# M720db.net
KiCad netlist of a schematic drawn in EAGLE
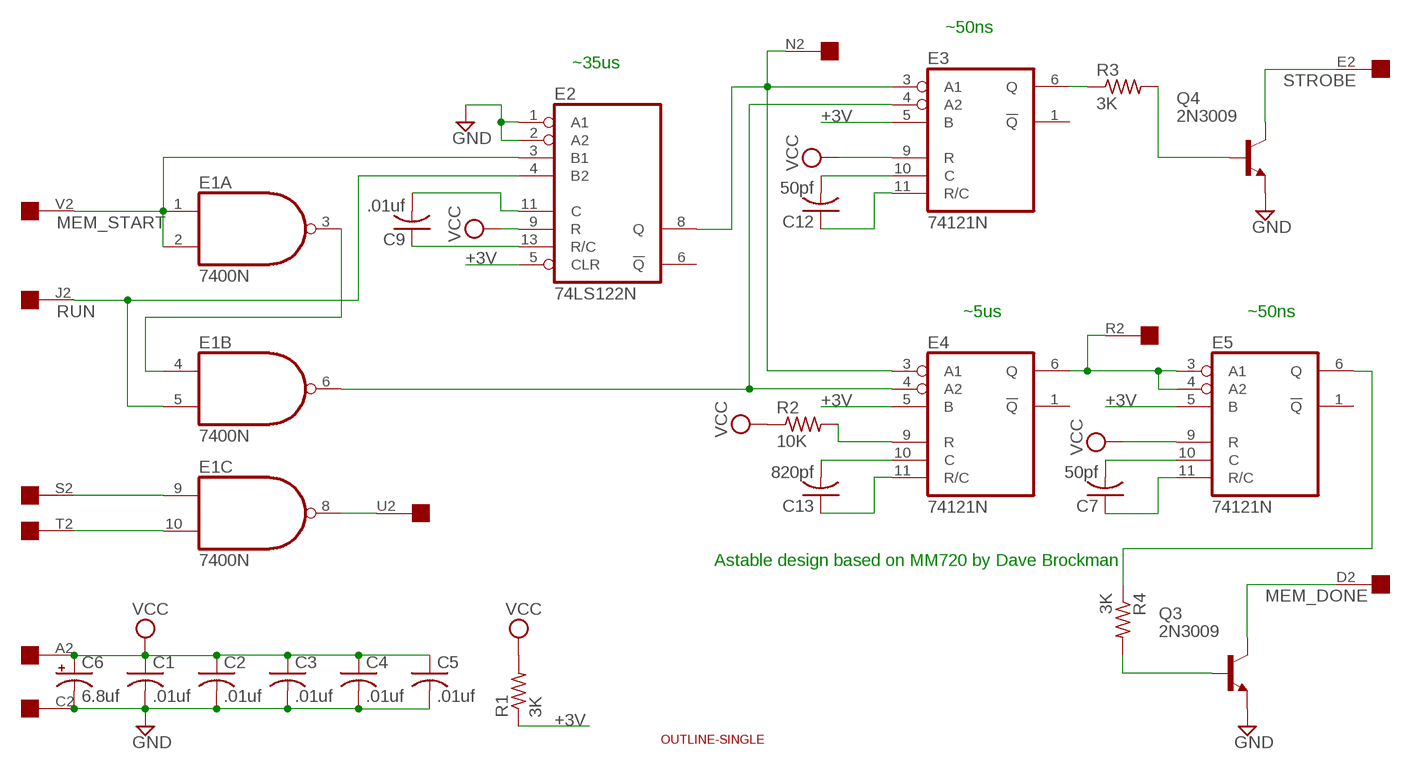
[diagram p0: schematic, sheet 1]

(export (version "E")
  (design (tool "Eeschema 10.0.6"))
  (components
    (comp (ref "C1")
      (value ".01uf")
      (footprint "eagle-import:C050-025X075")
      (libsource (lib "eagle-import") (part "C-US050-025X075"))
    )
    (comp (ref "C2")
      (value ".01uf")
      (footprint "eagle-import:C050-025X075")
      (libsource (lib "eagle-import") (part "C-US050-025X075"))
    )
    (comp (ref "C3")
      (value ".01uf")
      (footprint "eagle-import:C050-025X075")
      (libsource (lib "eagle-import") (part "C-US050-025X075"))
    )
    (comp (ref "C4")
      (value ".01uf")
      (footprint "eagle-import:C050-025X075")
      (libsource (lib "eagle-import") (part "C-US050-025X075"))
    )
    (comp (ref "C5")
      (value ".01uf")
      (footprint "eagle-import:C050-025X075")
      (libsource (lib "eagle-import") (part "C-US050-025X075"))
    )
    (comp (ref "C6")
      (value "6.8uf")
      (footprint "eagle-import:E15-5")
      (libsource (lib "eagle-import") (part "CPOL-USE15-5AXIAL"))
    )
    (comp (ref "C7")
      (value "50pf")
      (footprint "eagle-import:C050-025X075")
      (libsource (lib "eagle-import") (part "C-US050-025X075"))
    )
    (comp (ref "C9")
      (value ".01uf")
      (footprint "eagle-import:C050-025X075")
      (libsource (lib "eagle-import") (part "C-US050-025X075"))
    )
    (comp (ref "C12")
      (value "50pf")
      (footprint "eagle-import:C050-025X075")
      (libsource (lib "eagle-import") (part "C-US050-025X075"))
    )
    (comp (ref "C13")
      (value "820pf")
      (footprint "eagle-import:C050-025X075")
      (libsource (lib "eagle-import") (part "C-US050-025X075"))
    )
    (comp (ref "E1")
      (value "7400N")
      (footprint "eagle-import:DIL14")
      (libsource (lib "eagle-import") (part "7400N"))
    )
    (comp (ref "E2")
      (value "74LS122N")
      (footprint "eagle-import:DIL14")
      (libsource (lib "eagle-import") (part "74122NLS"))
    )
    (comp (ref "E3")
      (value "74121N")
      (footprint "eagle-import:DIL14")
      (libsource (lib "eagle-import") (part "74121N"))
    )
    (comp (ref "E4")
      (value "74121N")
      (footprint "eagle-import:DIL14")
      (libsource (lib "eagle-import") (part "74121N"))
    )
    (comp (ref "E5")
      (value "74121N")
      (footprint "eagle-import:DIL14")
      (libsource (lib "eagle-import") (part "74121N"))
    )
    (comp (ref "Q3")
      (value "2N3009")
      (footprint "eagle-import:TO5")
      (libsource (lib "eagle-import") (part "2N2405"))
    )
    (comp (ref "Q4")
      (value "2N3009")
      (footprint "eagle-import:TO5")
      (libsource (lib "eagle-import") (part "2N2405"))
    )
    (comp (ref "R1")
      (value "3K")
      (footprint "eagle-import:0207_10")
      (libsource (lib "eagle-import") (part "R-US_0207/10"))
    )
    (comp (ref "R2")
      (value "10K")
      (footprint "eagle-import:0207_10")
      (libsource (lib "eagle-import") (part "R-US_0207/10"))
    )
    (comp (ref "R3")
      (value "3K")
      (footprint "eagle-import:0207_10")
      (libsource (lib "eagle-import") (part "R-US_0207/10"))
    )
    (comp (ref "R4")
      (value "3K")
      (footprint "eagle-import:0207_10")
      (libsource (lib "eagle-import") (part "R-US_0207/10"))
    )
    (comp (ref "U$1")
      (value "OUTLINE-SINGLE")
      (footprint "eagle-import:SINGLE")
      (libsource (lib "eagle-import") (part "OUTLINE-SINGLE"))
    )
    (comp (ref "U$3")
      (value "EDGE-1")
      (footprint "eagle-import:EDGE-CON1")
      (libsource (lib "eagle-import") (part "EDGE-1"))
    )
  )
  (nets
    (net (code "1") (name "/+3V") (class "Default")
      (node (ref "E2") (pin "5") (pinfunction "CLR_5") (pintype "input"))
      (node (ref "E3") (pin "5") (pinfunction "B_5") (pintype "input"))
      (node (ref "E4") (pin "5") (pinfunction "B_5") (pintype "input"))
      (node (ref "E5") (pin "5") (pinfunction "B_5") (pintype "input"))
      (node (ref "R1") (pin "1") (pinfunction "1_1") (pintype "passive"))
    )
    (net (code "2") (name "/MEM_DONE") (class "Default")
      (node (ref "Q3") (pin "3") (pinfunction "C_3") (pintype "passive"))
      (node (ref "U$3") (pin "D2") (pinfunction "1_D2") (pintype "bidirectional"))
    )
    (net (code "3") (name "/MEM_START") (class "Default")
      (node (ref "E1") (pin "1") (pinfunction "I0_1") (pintype "input"))
      (node (ref "E1") (pin "2") (pinfunction "I1_2") (pintype "input"))
      (node (ref "E2") (pin "3") (pinfunction "B1_3") (pintype "input"))
      (node (ref "U$3") (pin "V2") (pinfunction "1_V2") (pintype "bidirectional"))
    )
    (net (code "4") (name "/RUN") (class "Default")
      (node (ref "E1") (pin "5") (pinfunction "I1_5") (pintype "input"))
      (node (ref "E2") (pin "4") (pinfunction "B2_4") (pintype "input"))
      (node (ref "U$3") (pin "J2") (pinfunction "1_J2") (pintype "bidirectional"))
    )
    (net (code "5") (name "/STROBE") (class "Default")
      (node (ref "Q4") (pin "3") (pinfunction "C_3") (pintype "passive"))
      (node (ref "U$3") (pin "E2") (pinfunction "1_E2") (pintype "bidirectional"))
    )
    (net (code "6") (name "GND") (class "Default")
      (node (ref "C1") (pin "2") (pinfunction "2_2") (pintype "passive"))
      (node (ref "C2") (pin "2") (pinfunction "2_2") (pintype "passive"))
      (node (ref "C3") (pin "2") (pinfunction "2_2") (pintype "passive"))
      (node (ref "C4") (pin "2") (pinfunction "2_2") (pintype "passive"))
      (node (ref "C5") (pin "2") (pinfunction "2_2") (pintype "passive"))
      (node (ref "C6") (pin "-") (pinfunction "-_-") (pintype "passive"))
      (node (ref "E2") (pin "1") (pinfunction "A1_1") (pintype "input"))
      (node (ref "E2") (pin "2") (pinfunction "A2_2") (pintype "input"))
      (node (ref "Q3") (pin "1") (pinfunction "E_1") (pintype "passive"))
      (node (ref "Q4") (pin "1") (pinfunction "E_1") (pintype "passive"))
      (node (ref "U$3") (pin "C2") (pinfunction "1_C2") (pintype "bidirectional"))
    )
    (net (code "7") (name "Net-(E1A-O)") (class "Default")
      (node (ref "E1") (pin "3") (pinfunction "O_3") (pintype "output"))
      (node (ref "E1") (pin "4") (pinfunction "I0_4") (pintype "input"))
    )
    (net (code "8") (name "Net-(E1B-O)") (class "Default")
      (node (ref "E1") (pin "6") (pinfunction "O_6") (pintype "output"))
      (node (ref "E3") (pin "4") (pinfunction "A2_4") (pintype "input"))
      (node (ref "E4") (pin "4") (pinfunction "A2_4") (pintype "input"))
    )
    (net (code "9") (name "Net-(E1C-I0)") (class "Default")
      (node (ref "E1") (pin "9") (pinfunction "I0_9") (pintype "input"))
      (node (ref "U$3") (pin "S2") (pinfunction "1_S2") (pintype "bidirectional"))
    )
    (net (code "10") (name "Net-(E1C-I1)") (class "Default")
      (node (ref "E1") (pin "10") (pinfunction "I1_10") (pintype "input"))
      (node (ref "U$3") (pin "T2") (pinfunction "1_T2") (pintype "bidirectional"))
    )
    (net (code "11") (name "Net-(E1C-O)") (class "Default")
      (node (ref "E1") (pin "8") (pinfunction "O_8") (pintype "output"))
      (node (ref "U$3") (pin "U2") (pinfunction "1_U2") (pintype "bidirectional"))
    )
    (net (code "12") (name "Net-(E2A-C)") (class "Default")
      (node (ref "C9") (pin "2") (pinfunction "2_2") (pintype "passive"))
      (node (ref "E2") (pin "11") (pinfunction "C_11") (pintype "input"))
    )
    (net (code "13") (name "Net-(E2A-Q)") (class "Default")
      (node (ref "E2") (pin "8") (pinfunction "Q_8") (pintype "output"))
      (node (ref "E3") (pin "3") (pinfunction "A1_3") (pintype "input"))
      (node (ref "E4") (pin "3") (pinfunction "A1_3") (pintype "input"))
      (node (ref "U$3") (pin "N2") (pinfunction "1_N2") (pintype "bidirectional"))
    )
    (net (code "14") (name "Net-(E2A-R{slash}C)") (class "Default")
      (node (ref "C9") (pin "1") (pinfunction "1_1") (pintype "passive"))
      (node (ref "E2") (pin "13") (pinfunction "R/C_13") (pintype "input"))
    )
    (net (code "15") (name "Net-(E3A-C)") (class "Default")
      (node (ref "C12") (pin "2") (pinfunction "2_2") (pintype "passive"))
      (node (ref "E3") (pin "10") (pinfunction "C_10") (pintype "input"))
    )
    (net (code "16") (name "Net-(E3A-Q)") (class "Default")
      (node (ref "E3") (pin "6") (pinfunction "Q_6") (pintype "output"))
      (node (ref "R3") (pin "1") (pinfunction "1_1") (pintype "passive"))
    )
    (net (code "17") (name "Net-(E3A-R{slash}C)") (class "Default")
      (node (ref "C12") (pin "1") (pinfunction "1_1") (pintype "passive"))
      (node (ref "E3") (pin "11") (pinfunction "R/C_11") (pintype "input"))
    )
    (net (code "18") (name "Net-(E4A-C)") (class "Default")
      (node (ref "C13") (pin "2") (pinfunction "2_2") (pintype "passive"))
      (node (ref "E4") (pin "10") (pinfunction "C_10") (pintype "input"))
    )
    (net (code "19") (name "Net-(E4A-Q)") (class "Default")
      (node (ref "E4") (pin "6") (pinfunction "Q_6") (pintype "output"))
      (node (ref "E5") (pin "3") (pinfunction "A1_3") (pintype "input"))
      (node (ref "E5") (pin "4") (pinfunction "A2_4") (pintype "input"))
      (node (ref "U$3") (pin "R2") (pinfunction "1_R2") (pintype "bidirectional"))
    )
    (net (code "20") (name "Net-(E4A-R)") (class "Default")
      (node (ref "E4") (pin "9") (pinfunction "R_9") (pintype "input"))
      (node (ref "R2") (pin "2") (pinfunction "2_2") (pintype "passive"))
    )
    (net (code "21") (name "Net-(E4A-R{slash}C)") (class "Default")
      (node (ref "C13") (pin "1") (pinfunction "1_1") (pintype "passive"))
      (node (ref "E4") (pin "11") (pinfunction "R/C_11") (pintype "input"))
    )
    (net (code "22") (name "Net-(E5A-C)") (class "Default")
      (node (ref "C7") (pin "2") (pinfunction "2_2") (pintype "passive"))
      (node (ref "E5") (pin "10") (pinfunction "C_10") (pintype "input"))
    )
    (net (code "23") (name "Net-(E5A-Q)") (class "Default")
      (node (ref "E5") (pin "6") (pinfunction "Q_6") (pintype "output"))
      (node (ref "R4") (pin "1") (pinfunction "1_1") (pintype "passive"))
    )
    (net (code "24") (name "Net-(E5A-R{slash}C)") (class "Default")
      (node (ref "C7") (pin "1") (pinfunction "1_1") (pintype "passive"))
      (node (ref "E5") (pin "11") (pinfunction "R/C_11") (pintype "input"))
    )
    (net (code "25") (name "Net-(Q3-B)") (class "Default")
      (node (ref "Q3") (pin "2") (pinfunction "B_2") (pintype "passive"))
      (node (ref "R4") (pin "2") (pinfunction "2_2") (pintype "passive"))
    )
    (net (code "26") (name "Net-(Q4-B)") (class "Default")
      (node (ref "Q4") (pin "2") (pinfunction "B_2") (pintype "passive"))
      (node (ref "R3") (pin "2") (pinfunction "2_2") (pintype "passive"))
    )
    (net (code "27") (name "VCC") (class "Default")
      (node (ref "C1") (pin "1") (pinfunction "1_1") (pintype "passive"))
      (node (ref "C2") (pin "1") (pinfunction "1_1") (pintype "passive"))
      (node (ref "C3") (pin "1") (pinfunction "1_1") (pintype "passive"))
      (node (ref "C4") (pin "1") (pinfunction "1_1") (pintype "passive"))
      (node (ref "C5") (pin "1") (pinfunction "1_1") (pintype "passive"))
      (node (ref "C6") (pin "+") (pinfunction "+_+") (pintype "passive"))
      (node (ref "E2") (pin "9") (pinfunction "R_9") (pintype "input"))
      (node (ref "E3") (pin "9") (pinfunction "R_9") (pintype "input"))
      (node (ref "E5") (pin "9") (pinfunction "R_9") (pintype "input"))
      (node (ref "R1") (pin "2") (pinfunction "2_2") (pintype "passive"))
      (node (ref "R2") (pin "1") (pinfunction "1_1") (pintype "passive"))
      (node (ref "U$3") (pin "A2") (pinfunction "1_A2") (pintype "bidirectional"))
    )
    (net (code "28") (name "unconnected-(E2A-~{Q}-Pad6)") (class "Default")
      (node (ref "E2") (pin "6") (pinfunction "~{Q}_6") (pintype "output"))
    )
    (net (code "29") (name "unconnected-(E3A-~{Q}-Pad1)") (class "Default")
      (node (ref "E3") (pin "1") (pinfunction "~{Q}_1") (pintype "output"))
    )
    (net (code "30") (name "unconnected-(E4A-~{Q}-Pad1)") (class "Default")
      (node (ref "E4") (pin "1") (pinfunction "~{Q}_1") (pintype "output"))
    )
    (net (code "31") (name "unconnected-(E5A-~{Q}-Pad1)") (class "Default")
      (node (ref "E5") (pin "1") (pinfunction "~{Q}_1") (pintype "output"))
    )
  )
)
